# Schematic.net
KiCad netlist of a schematic drawn in EAGLE
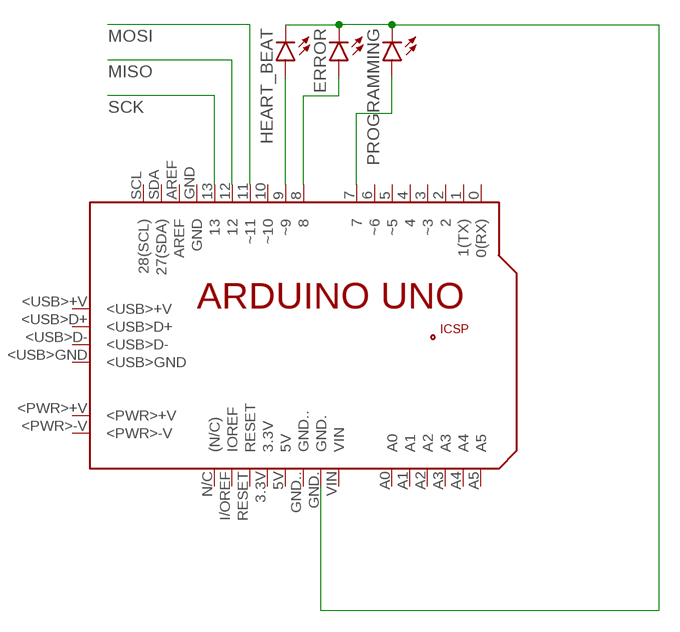
[diagram p0: schematic, sheet 1]

(export (version "E")
  (design (tool "Eeschema 10.0.6"))
  (components
    (comp (ref "ERROR")
      (value "LED5MM")
      (footprint "eagle-import:LED5MM")
      (libsource (lib "eagle-import") (part "LED5MM"))
    )
    (comp (ref "HEART_BEAT")
      (value "LED5MM")
      (footprint "eagle-import:LED5MM")
      (libsource (lib "eagle-import") (part "LED5MM"))
    )
    (comp (ref "PCB1")
      (value "ARDUINO_UNO")
      (footprint "eagle-import:ARDUINO_UNO")
      (libsource (lib "eagle-import") (part "ARDUINO_UNO"))
    )
    (comp (ref "PROGRAMMING")
      (value "LED5MM")
      (footprint "eagle-import:LED5MM")
      (libsource (lib "eagle-import") (part "LED5MM"))
    )
  )
  (nets
    (net (code "1") (name "/MISO") (class "Default")
      (node (ref "PCB1") (pin "12") (pinfunction "12_12") (pintype "bidirectional"))
    )
    (net (code "2") (name "/MOSI") (class "Default")
      (node (ref "PCB1") (pin "11") (pinfunction "~{11}_11") (pintype "bidirectional"))
    )
    (net (code "3") (name "/SCK") (class "Default")
      (node (ref "PCB1") (pin "13") (pinfunction "13_13") (pintype "bidirectional"))
    )
    (net (code "4") (name "Net-(ERROR-C)") (class "Default")
      (node (ref "ERROR") (pin "K") (pinfunction "C_K") (pintype "passive"))
      (node (ref "HEART_BEAT") (pin "K") (pinfunction "C_K") (pintype "passive"))
      (node (ref "PCB1") (pin "GND.") (pinfunction "GND._GND.") (pintype "bidirectional"))
      (node (ref "PROGRAMMING") (pin "K") (pinfunction "C_K") (pintype "passive"))
    )
    (net (code "5") (name "Net-(ERROR-PadA)") (class "Default")
      (node (ref "ERROR") (pin "A") (pinfunction "A_A") (pintype "passive"))
      (node (ref "PCB1") (pin "8") (pinfunction "8_8") (pintype "bidirectional"))
    )
    (net (code "6") (name "Net-(PCB1-Pad7)") (class "Default")
      (node (ref "PCB1") (pin "7") (pinfunction "7_7") (pintype "bidirectional"))
      (node (ref "PROGRAMMING") (pin "A") (pinfunction "A_A") (pintype "passive"))
    )
    (net (code "7") (name "Net-(PCB1-~{9})") (class "Default")
      (node (ref "HEART_BEAT") (pin "A") (pinfunction "A_A") (pintype "passive"))
      (node (ref "PCB1") (pin "9") (pinfunction "~{9}_9") (pintype "bidirectional"))
    )
    (net (code "8") (name "unconnected-(PCB1-(N{slash}C)-PadN{slash}C)") (class "Default")
      (node (ref "PCB1") (pin "N/C") (pinfunction "(N/C)_N/C") (pintype "bidirectional"))
    )
    (net (code "9") (name "unconnected-(PCB1-0(RX)-Pad0)") (class "Default")
      (node (ref "PCB1") (pin "0") (pinfunction "0(RX)_0") (pintype "bidirectional"))
    )
    (net (code "10") (name "unconnected-(PCB1-1(TX)-Pad1)") (class "Default")
      (node (ref "PCB1") (pin "1") (pinfunction "1(TX)_1") (pintype "bidirectional"))
    )
    (net (code "11") (name "unconnected-(PCB1-27(SDA)-PadSDA)") (class "Default")
      (node (ref "PCB1") (pin "SDA") (pinfunction "27(SDA)_SDA") (pintype "bidirectional"))
    )
    (net (code "12") (name "unconnected-(PCB1-28(SCL)-PadSCL)") (class "Default")
      (node (ref "PCB1") (pin "SCL") (pinfunction "28(SCL)_SCL") (pintype "bidirectional"))
    )
    (net (code "13") (name "unconnected-(PCB1-IOREF-PadI{slash}OREF)") (class "Default")
      (node (ref "PCB1") (pin "I/OREF") (pinfunction "IOREF_I/OREF") (pintype "bidirectional"))
    )
    (net (code "14") (name "unconnected-(PCB1-Pad+5V)") (class "Default")
      (node (ref "PCB1") (pin "+5V") (pinfunction "+5V_+5V") (pintype "bidirectional"))
    )
    (net (code "15") (name "unconnected-(PCB1-Pad2)") (class "Default")
      (node (ref "PCB1") (pin "2") (pinfunction "2_2") (pintype "bidirectional"))
    )
    (net (code "16") (name "unconnected-(PCB1-Pad3.3V)") (class "Default")
      (node (ref "PCB1") (pin "3.3V") (pinfunction "3.3V_3.3V") (pintype "bidirectional"))
    )
    (net (code "17") (name "unconnected-(PCB1-Pad4)") (class "Default")
      (node (ref "PCB1") (pin "4") (pinfunction "4_4") (pintype "bidirectional"))
    )
    (net (code "18") (name "unconnected-(PCB1-Pad5V)") (class "Default")
      (node (ref "PCB1") (pin "5V") (pinfunction "5V_5V") (pintype "bidirectional"))
    )
    (net (code "19") (name "unconnected-(PCB1-Pad<PWR>+V)") (class "Default")
      (node (ref "PCB1") (pin "<PWR>+V") (pinfunction "<PWR>+V_<PWR>+V") (pintype "bidirectional"))
    )
    (net (code "20") (name "unconnected-(PCB1-Pad<PWR>-V)") (class "Default")
      (node (ref "PCB1") (pin "<PWR>-V") (pinfunction "<PWR>-V_<PWR>-V") (pintype "bidirectional"))
    )
    (net (code "21") (name "unconnected-(PCB1-Pad<USB>+V)") (class "Default")
      (node (ref "PCB1") (pin "<USB>+V") (pinfunction "<USB>+V_<USB>+V") (pintype "bidirectional"))
    )
    (net (code "22") (name "unconnected-(PCB1-Pad<USB>D+)") (class "Default")
      (node (ref "PCB1") (pin "<USB>D+") (pinfunction "<USB>D+_<USB>D+") (pintype "bidirectional"))
    )
    (net (code "23") (name "unconnected-(PCB1-Pad<USB>D-)") (class "Default")
      (node (ref "PCB1") (pin "<USB>D-") (pinfunction "<USB>D-_<USB>D-") (pintype "bidirectional"))
    )
    (net (code "24") (name "unconnected-(PCB1-Pad<USB>GND)") (class "Default")
      (node (ref "PCB1") (pin "<USB>GND") (pinfunction "<USB>GND_<USB>GND") (pintype "bidirectional"))
    )
    (net (code "25") (name "unconnected-(PCB1-PadA0)") (class "Default")
      (node (ref "PCB1") (pin "A0") (pinfunction "A0_A0") (pintype "bidirectional"))
    )
    (net (code "26") (name "unconnected-(PCB1-PadA1)") (class "Default")
      (node (ref "PCB1") (pin "A1") (pinfunction "A1_A1") (pintype "bidirectional"))
    )
    (net (code "27") (name "unconnected-(PCB1-PadA2)") (class "Default")
      (node (ref "PCB1") (pin "A2") (pinfunction "A2_A2") (pintype "bidirectional"))
    )
    (net (code "28") (name "unconnected-(PCB1-PadA3)") (class "Default")
      (node (ref "PCB1") (pin "A3") (pinfunction "A3_A3") (pintype "bidirectional"))
    )
    (net (code "29") (name "unconnected-(PCB1-PadA4)") (class "Default")
      (node (ref "PCB1") (pin "A4") (pinfunction "A4_A4") (pintype "bidirectional"))
    )
    (net (code "30") (name "unconnected-(PCB1-PadA5)") (class "Default")
      (node (ref "PCB1") (pin "A5") (pinfunction "A5_A5") (pintype "bidirectional"))
    )
    (net (code "31") (name "unconnected-(PCB1-PadAREF)") (class "Default")
      (node (ref "PCB1") (pin "AREF") (pinfunction "AREF_AREF") (pintype "bidirectional"))
    )
    (net (code "32") (name "unconnected-(PCB1-PadGND)") (class "Default")
      (node (ref "PCB1") (pin "GND") (pinfunction "GND_GND") (pintype "bidirectional"))
    )
    (net (code "33") (name "unconnected-(PCB1-PadGND..)") (class "Default")
      (node (ref "PCB1") (pin "GND..") (pinfunction "GND.._GND..") (pintype "bidirectional"))
    )
    (net (code "34") (name "unconnected-(PCB1-PadGND_)") (class "Default")
      (node (ref "PCB1") (pin "GND_") (pinfunction "GND__GND_") (pintype "bidirectional"))
    )
    (net (code "35") (name "unconnected-(PCB1-PadMISO)") (class "Default")
      (node (ref "PCB1") (pin "MISO") (pinfunction "MISO_MISO") (pintype "bidirectional"))
    )
    (net (code "36") (name "unconnected-(PCB1-PadMOSI)") (class "Default")
      (node (ref "PCB1") (pin "MOSI") (pinfunction "MOSI_MOSI") (pintype "bidirectional"))
    )
    (net (code "37") (name "unconnected-(PCB1-PadRESET)") (class "Default")
      (node (ref "PCB1") (pin "RESET") (pinfunction "RESET_RESET") (pintype "bidirectional"))
    )
    (net (code "38") (name "unconnected-(PCB1-PadRESET.)") (class "Default")
      (node (ref "PCB1") (pin "RESET.") (pinfunction "RESET._RESET.") (pintype "bidirectional"))
    )
    (net (code "39") (name "unconnected-(PCB1-PadSCK)") (class "Default")
      (node (ref "PCB1") (pin "SCK") (pinfunction "SCK_SCK") (pintype "bidirectional"))
    )
    (net (code "40") (name "unconnected-(PCB1-PadVIN)") (class "Default")
      (node (ref "PCB1") (pin "VIN") (pinfunction "VIN_VIN") (pintype "bidirectional"))
    )
    (net (code "41") (name "unconnected-(PCB1-~{3}-Pad3)") (class "Default")
      (node (ref "PCB1") (pin "3") (pinfunction "~{3}_3") (pintype "bidirectional"))
    )
    (net (code "42") (name "unconnected-(PCB1-~{5}-Pad5)") (class "Default")
      (node (ref "PCB1") (pin "5") (pinfunction "~{5}_5") (pintype "bidirectional"))
    )
    (net (code "43") (name "unconnected-(PCB1-~{6}-Pad6)") (class "Default")
      (node (ref "PCB1") (pin "6") (pinfunction "~{6}_6") (pintype "bidirectional"))
    )
    (net (code "44") (name "unconnected-(PCB1-~{10}-Pad10)") (class "Default")
      (node (ref "PCB1") (pin "10") (pinfunction "~{10}_10") (pintype "bidirectional"))
    )
  )
)
